# EV2760-VT-00A.net
KiCad netlist of a schematic drawn in Altium Designer
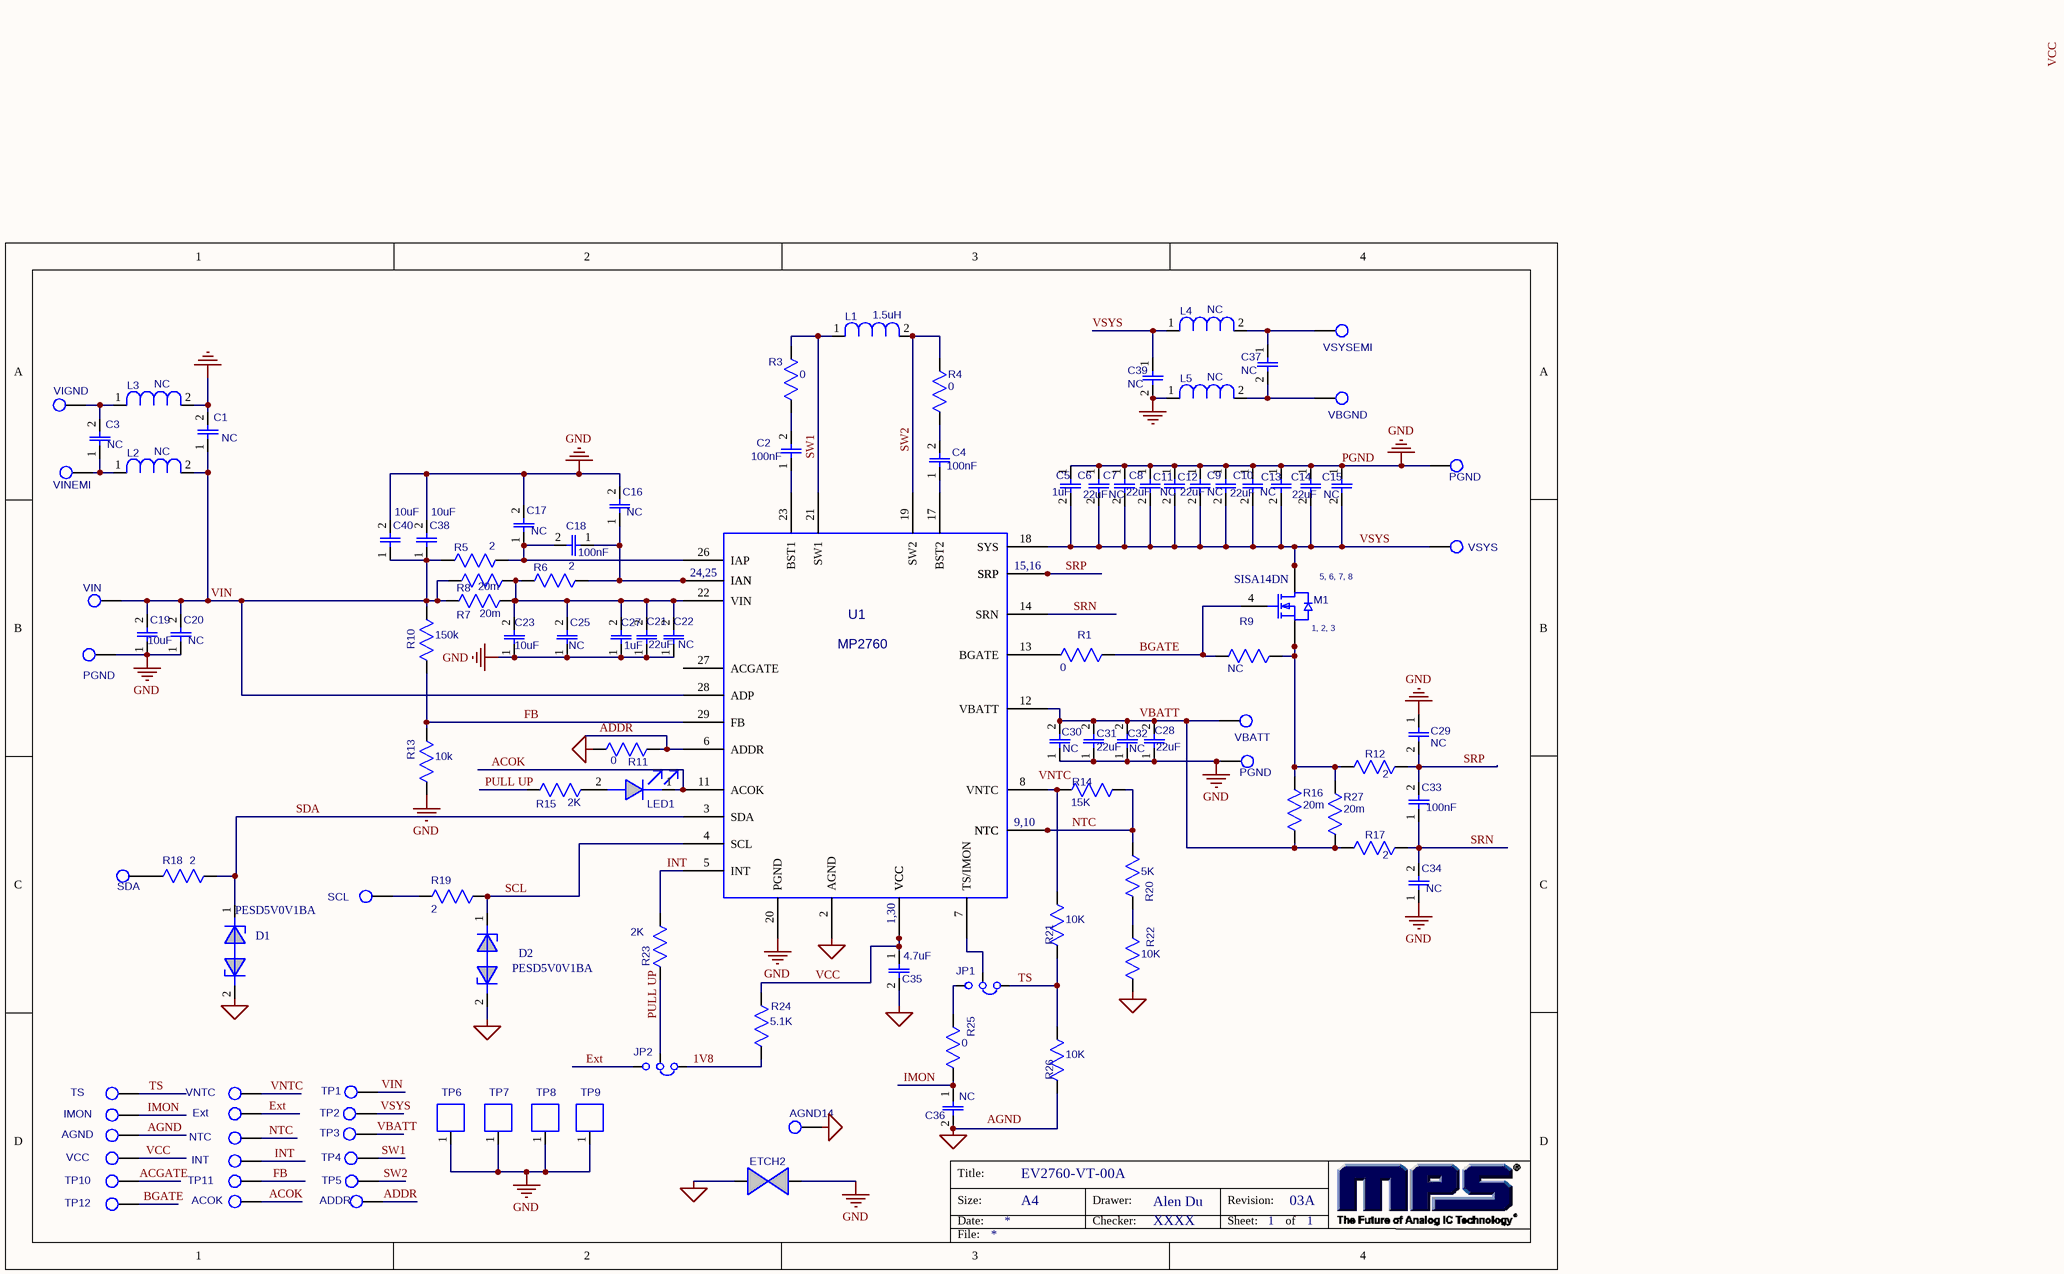
[diagram p0: EV2760-VT-00A.SchDoc]

(export (version "E")
  (design (tool "Eeschema 10.0.6"))
  (components
    (comp (ref "ACOK")
      (value "{Package}")
      (footprint "CONN/TP")
      (description "Connector;")
      (fields (field (name "MANUFACTURER") "{Manufacturer}") (field (name "PART NUMBER") "17.0017"))
      (libsource (lib "MPSLab") (part "CONN/TP"))
    )
    (comp (ref "ADDR")
      (value "{Package}")
      (footprint "CONN/TP")
      (description "Connector;")
      (fields (field (name "MANUFACTURER") "{Manufacturer}") (field (name "PART NUMBER") "17.0017"))
      (libsource (lib "MPSLab") (part "CONN/TP"))
    )
    (comp (ref "AGND")
      (value "{Package}")
      (footprint "CONN/TP")
      (description "Connector;")
      (fields (field (name "MANUFACTURER") "{Manufacturer}") (field (name "PART NUMBER") "17.0017"))
      (libsource (lib "MPSLab") (part "CONN/TP"))
    )
    (comp (ref "AGND14")
      (value "{Package}")
      (footprint "CONN/TP")
      (description "Connector;")
      (fields (field (name "MANUFACTURER") "{Manufacturer}") (field (name "PART NUMBER") "17.0017"))
      (libsource (lib "MPSLab") (part "CONN/TP"))
    )
    (comp (ref "C1")
      (value "NC")
      (footprint "CAP/0805")
      (description "Capacitor;25V;X5R")
      (fields (field (name "MANUFACTURER") "{Manufacturer}") (field (name "PART NUMBER") "07.0970"))
      (libsource (lib "MPSLab") (part "CAP/0805"))
    )
    (comp (ref "C2")
      (value "100nF")
      (footprint "CAP/0603")
      (description "Capacitor;25V;X5R")
      (fields (field (name "MANUFACTURER") "{Manufacturer}") (field (name "PART NUMBER") "07.0969"))
      (libsource (lib "MPSLab") (part "CAP/0603"))
    )
    (comp (ref "C3")
      (value "NC")
      (footprint "CAP/0805")
      (description "Capacitor;25V;X5R")
      (fields (field (name "MANUFACTURER") "{Manufacturer}") (field (name "PART NUMBER") "07.0970"))
      (libsource (lib "MPSLab") (part "CAP/0805"))
    )
    (comp (ref "C4")
      (value "100nF")
      (footprint "CAP/0603")
      (description "Capacitor;25V;X5R")
      (fields (field (name "MANUFACTURER") "{Manufacturer}") (field (name "PART NUMBER") "07.0969"))
      (libsource (lib "MPSLab") (part "CAP/0603"))
    )
    (comp (ref "C5")
      (value "1uF")
      (footprint "CAP/0603")
      (description "Ceramic Capacitor;25V;X7R;0603;")
      (fields (field (name "MANUFACTURER") "{Manufacturer}") (field (name "PART NUMBER") "07.0042"))
      (libsource (lib "MPSLab") (part "CAP/0603"))
    )
    (comp (ref "C6")
      (value "22uF")
      (footprint "CAP/0805")
      (description "Capacitor;25V;X5R")
      (fields (field (name "MANUFACTURER") "{Manufacturer}") (field (name "PART NUMBER") "07.1006"))
      (libsource (lib "MPSLab") (part "CAP/0805"))
    )
    (comp (ref "C7")
      (value "NC")
      (footprint "CAP/0805")
      (description "Capacitor;25V;X5R")
      (fields (field (name "MANUFACTURER") "{Manufacturer}") (field (name "PART NUMBER") "07.1006"))
      (libsource (lib "MPSLab") (part "CAP/0805"))
    )
    (comp (ref "C8")
      (value "22uF")
      (footprint "CAP/0805")
      (description "Capacitor;25V;X5R")
      (fields (field (name "MANUFACTURER") "{Manufacturer}") (field (name "PART NUMBER") "07.1006"))
      (libsource (lib "MPSLab") (part "CAP/0805"))
    )
    (comp (ref "C9")
      (value "NC")
      (footprint "CAP/0805")
      (description "Capacitor;25V;X5R")
      (fields (field (name "MANUFACTURER") "{Manufacturer}") (field (name "PART NUMBER") "07.1006"))
      (libsource (lib "MPSLab") (part "CAP/0805"))
    )
    (comp (ref "C10")
      (value "22uF")
      (footprint "CAP/0805")
      (description "Capacitor;25V;X5R")
      (fields (field (name "MANUFACTURER") "{Manufacturer}") (field (name "PART NUMBER") "07.1006"))
      (libsource (lib "MPSLab") (part "CAP/0805"))
    )
    (comp (ref "C11")
      (value "NC")
      (footprint "CAP/0805")
      (description "Capacitor;25V;X7R")
      (fields (field (name "MANUFACTURER") "{Manufacturer}") (field (name "PART NUMBER") "07.1121"))
      (libsource (lib "MPSLab") (part "CAP/0805"))
    )
    (comp (ref "C12")
      (value "22uF")
      (footprint "CAP/0805")
      (description "Capacitor;25V;X5R")
      (fields (field (name "MANUFACTURER") "{Manufacturer}") (field (name "PART NUMBER") "07.1006"))
      (libsource (lib "MPSLab") (part "CAP/0805"))
    )
    (comp (ref "C13")
      (value "NC")
      (footprint "CAP/0805")
      (description "Capacitor;25V;X5R")
      (fields (field (name "MANUFACTURER") "{Manufacturer}") (field (name "PART NUMBER") "07.1006"))
      (libsource (lib "MPSLab") (part "CAP/0805"))
    )
    (comp (ref "C14")
      (value "22uF")
      (footprint "CAP/0805")
      (description "Ceramic Capacitor;25V;X7R;0603;")
      (fields (field (name "MANUFACTURER") "{Manufacturer}") (field (name "PART NUMBER") "07.0042"))
      (libsource (lib "MPSLab") (part "CAP/0603"))
    )
    (comp (ref "C15")
      (value "NC")
      (footprint "CAP/0603")
      (description "Ceramic Capacitor;25V;X7R;0603;")
      (fields (field (name "MANUFACTURER") "{Manufacturer}") (field (name "PART NUMBER") "07.0042"))
      (libsource (lib "MPSLab") (part "CAP/0603"))
    )
    (comp (ref "C16")
      (value "NC")
      (footprint "CAP/0603")
      (description "Ceramic Capacitor;25V;X7R;0603;")
      (fields (field (name "MANUFACTURER") "{Manufacturer}") (field (name "PART NUMBER") "07.0042"))
      (libsource (lib "MPSLab") (part "CAP/0603"))
    )
    (comp (ref "C17")
      (value "NC")
      (footprint "CAP/0603")
      (description "Ceramic Capacitor;25V;X7R;0603;")
      (fields (field (name "MANUFACTURER") "{Manufacturer}") (field (name "PART NUMBER") "07.0042"))
      (libsource (lib "MPSLab") (part "CAP/0603"))
    )
    (comp (ref "C18")
      (value "100nF")
      (footprint "CAP/0603")
      (description "Ceramic Capacitor;50V;C0G;0603;")
      (fields (field (name "MANUFACTURER") "{Manufacturer}") (field (name "PART NUMBER") "07.0074"))
      (libsource (lib "MPSLab") (part "CAP/0603"))
    )
    (comp (ref "C19")
      (value "10uF")
      (footprint "CAP/0805")
      (description "Capacitor;25V;X5R")
      (fields (field (name "MANUFACTURER") "{Manufacturer}") (field (name "PART NUMBER") "07.0970"))
      (libsource (lib "MPSLab") (part "CAP/0805"))
    )
    (comp (ref "C20")
      (value "NC")
      (footprint "CAP/0805")
      (description "Capacitor;25V;X5R")
      (fields (field (name "MANUFACTURER") "{Manufacturer}") (field (name "PART NUMBER") "07.0970"))
      (libsource (lib "MPSLab") (part "CAP/0805"))
    )
    (comp (ref "C21")
      (value "22uF")
      (footprint "CAP/0603")
      (description "Ceramic Capacitor;25V;X7R;0603;")
      (fields (field (name "MANUFACTURER") "{Manufacturer}") (field (name "PART NUMBER") "07.0042"))
      (libsource (lib "MPSLab") (part "CAP/0603"))
    )
    (comp (ref "C22")
      (value "NC")
      (footprint "CAP/0603")
      (description "Ceramic Capacitor;25V;X7R;0603;")
      (fields (field (name "MANUFACTURER") "{Manufacturer}") (field (name "PART NUMBER") "07.0042"))
      (libsource (lib "MPSLab") (part "CAP/0603"))
    )
    (comp (ref "C23")
      (value "10uF")
      (footprint "CAP/0805")
      (description "Capacitor;25V;X5R")
      (fields (field (name "MANUFACTURER") "{Manufacturer}") (field (name "PART NUMBER") "07.0970"))
      (libsource (lib "MPSLab") (part "CAP/0805"))
    )
    (comp (ref "C25")
      (value "NC")
      (footprint "CAP/0805")
      (description "Capacitor;25V;X5R")
      (fields (field (name "MANUFACTURER") "{Manufacturer}") (field (name "PART NUMBER") "07.0970"))
      (libsource (lib "MPSLab") (part "CAP/0805"))
    )
    (comp (ref "C27")
      (value "1uF")
      (footprint "CAP/0603")
      (description "Ceramic Capacitor;25V;X7R;0603;")
      (fields (field (name "MANUFACTURER") "{Manufacturer}") (field (name "PART NUMBER") "07.0042"))
      (libsource (lib "MPSLab") (part "CAP/0603"))
    )
    (comp (ref "C28")
      (value "22uF")
      (footprint "CAP/0805")
      (description "Capacitor;25V;X5R")
      (fields (field (name "MANUFACTURER") "{Manufacturer}") (field (name "PART NUMBER") "07.1006"))
      (libsource (lib "MPSLab") (part "CAP/0805"))
    )
    (comp (ref "C29")
      (value "NC")
      (footprint "CAP/0603")
      (description "Ceramic Capacitor;25V;X7R;0603;")
      (fields (field (name "MANUFACTURER") "{Manufacturer}") (field (name "PART NUMBER") "07.0042"))
      (libsource (lib "MPSLab") (part "CAP/0603"))
    )
    (comp (ref "C30")
      (value "NC")
      (footprint "CAP/0805")
      (description "Capacitor;25V;X7R")
      (fields (field (name "MANUFACTURER") "{Manufacturer}") (field (name "PART NUMBER") "07.1121"))
      (libsource (lib "MPSLab") (part "CAP/0805"))
    )
    (comp (ref "C31")
      (value "22uF")
      (footprint "CAP/0805")
      (description "Capacitor;25V;X5R")
      (fields (field (name "MANUFACTURER") "{Manufacturer}") (field (name "PART NUMBER") "07.1006"))
      (libsource (lib "MPSLab") (part "CAP/0805"))
    )
    (comp (ref "C32")
      (value "NC")
      (footprint "CAP/0805")
      (description "Capacitor;25V;X5R")
      (fields (field (name "MANUFACTURER") "{Manufacturer}") (field (name "PART NUMBER") "07.1006"))
      (libsource (lib "MPSLab") (part "CAP/0805"))
    )
    (comp (ref "C33")
      (value "100nF")
      (footprint "CAP/0603")
      (description "Ceramic Capacitor;25V;X7R;0603;")
      (fields (field (name "MANUFACTURER") "{Manufacturer}") (field (name "PART NUMBER") "07.0042"))
      (libsource (lib "MPSLab") (part "CAP/0603"))
    )
    (comp (ref "C34")
      (value "NC")
      (footprint "CAP/0603")
      (description "Ceramic Capacitor;25V;X7R;0603;")
      (fields (field (name "MANUFACTURER") "{Manufacturer}") (field (name "PART NUMBER") "07.0042"))
      (libsource (lib "MPSLab") (part "CAP/0603"))
    )
    (comp (ref "C35")
      (value "4.7uF")
      (footprint "CAP/0603")
      (description "Ceramic Capacitor;50V;X7R;0603;")
      (fields (field (name "MANUFACTURER") "{Manufacturer}") (field (name "PART NUMBER") "07.0015"))
      (libsource (lib "MPSLab") (part "CAP/0603"))
    )
    (comp (ref "C36")
      (value "NC")
      (footprint "CAP/0603")
      (description "Ceramic Capacitor;50V;X7R;0603;")
      (fields (field (name "MANUFACTURER") "{Manufacturer}") (field (name "PART NUMBER") "07.0015"))
      (libsource (lib "MPSLab") (part "CAP/0603"))
    )
    (comp (ref "C37")
      (value "NC")
      (footprint "CAP/0603")
      (description "Ceramic Capacitor;25V;X7R;0603;")
      (fields (field (name "MANUFACTURER") "{Manufacturer}") (field (name "PART NUMBER") "07.0042"))
      (libsource (lib "MPSLab") (part "CAP/0603"))
    )
    (comp (ref "C38")
      (value "10uF")
      (footprint "CAP/0805")
      (description "Capacitor;25V;X5R")
      (fields (field (name "MANUFACTURER") "{Manufacturer}") (field (name "PART NUMBER") "07.0970"))
      (libsource (lib "MPSLab") (part "CAP/0805"))
    )
    (comp (ref "C39")
      (value "NC")
      (footprint "CAP/0603")
      (description "Ceramic Capacitor;25V;X7R;0603;")
      (fields (field (name "MANUFACTURER") "{Manufacturer}") (field (name "PART NUMBER") "07.0042"))
      (libsource (lib "MPSLab") (part "CAP/0603"))
    )
    (comp (ref "C40")
      (value "10uF")
      (footprint "CAP/0805")
      (description "Capacitor;25V;X5R")
      (fields (field (name "MANUFACTURER") "{Manufacturer}") (field (name "PART NUMBER") "07.0970"))
      (libsource (lib "MPSLab") (part "CAP/0805"))
    )
    (comp (ref "D1")
      (value "PESD5V0V1BA")
      (footprint "Diodes:SOD323/PESD5V0V1BA")
      (libsource (lib "Sheet1") (part "PESD5V0V1BA"))
    )
    (comp (ref "D2")
      (value "PESD5V0V1BA")
      (footprint "Diodes:SOD323/PESD5V0V1BA")
      (libsource (lib "Sheet1") (part "PESD5V0V1BA"))
    )
    (comp (ref "ETCH2")
      (value "ETCH0402")
      (footprint "ETCH0603")
      (description "{Description}")
      (fields (field (name "MANUFACTURER") "{Manufacturer}"))
      (libsource (lib "MPS_RESISTOR") (part "ETCH0402"))
    )
    (comp (ref "Ext")
      (value "{Package}")
      (footprint "CONN/TP")
      (description "Connector;")
      (fields (field (name "MANUFACTURER") "{Manufacturer}") (field (name "PART NUMBER") "17.0017"))
      (libsource (lib "MPSLab") (part "CONN/TP"))
    )
    (comp (ref "IMON")
      (value "{Package}")
      (footprint "CONN/TP")
      (description "Connector;")
      (fields (field (name "MANUFACTURER") "{Manufacturer}") (field (name "PART NUMBER") "17.0017"))
      (libsource (lib "MPSLab") (part "CONN/TP"))
    )
    (comp (ref "INT")
      (value "{Package}")
      (footprint "CONN/TP")
      (description "Connector;")
      (fields (field (name "MANUFACTURER") "{Manufacturer}") (field (name "PART NUMBER") "17.0017"))
      (libsource (lib "MPSLab") (part "CONN/TP"))
    )
    (comp (ref "JP1")
      (value "JUMPER/3PIN/DIP/2.54MM/B")
      (footprint "CONN/DIP/3PIN/2.54MM/A")
      (description "{Description}")
      (fields (field (name "MANUFACTURER") "{Manufacturer}"))
      (libsource (lib "Jumper") (part "JUMPER/3PIN/DIP/2.54MM/B"))
    )
    (comp (ref "JP2")
      (value "JUMPER/3PIN/DIP/2.54MM/B")
      (footprint "CONN/DIP/3PIN/2.54MM/A")
      (description "{Description}")
      (fields (field (name "MANUFACTURER") "{Manufacturer}"))
      (libsource (lib "Jumper") (part "JUMPER/3PIN/DIP/2.54MM/B"))
    )
    (comp (ref "L1")
      (value "1.5uH")
      (footprint "IND/Wurth/7447745022")
      (description "Inductor;2.2uH;0.0173ohms;8.2A")
      (fields (field (name "MANUFACTURER") "{Manufacturer}") (field (name "PART NUMBER") "03.0763"))
      (libsource (lib "MPSLab") (part "IND/TDK/SPM6530T-2R2M"))
    )
    (comp (ref "L2")
      (value "NC")
      (footprint "RES/0805")
      (description "Inductor;2.2uH;0.0173ohms;8.2A")
      (fields (field (name "MANUFACTURER") "{Manufacturer}") (field (name "PART NUMBER") "03.0616"))
      (libsource (lib "MPSLab") (part "IND/TDK/SPM6530T-2R2M"))
    )
    (comp (ref "L3")
      (value "NC")
      (footprint "RES/0805")
      (description "Inductor;2.2uH;0.0173ohms;8.2A")
      (fields (field (name "MANUFACTURER") "{Manufacturer}") (field (name "PART NUMBER") "03.0616"))
      (libsource (lib "MPSLab") (part "IND/TDK/SPM6530T-2R2M"))
    )
    (comp (ref "L4")
      (value "NC")
      (footprint "RES/0805")
      (description "Inductor;2.2uH;0.0173ohms;8.2A")
      (fields (field (name "MANUFACTURER") "{Manufacturer}") (field (name "PART NUMBER") "03.0616"))
      (libsource (lib "MPSLab") (part "IND/TDK/SPM6530T-2R2M"))
    )
    (comp (ref "L5")
      (value "NC")
      (footprint "RES/0805")
      (description "Inductor;2.2uH;0.0173ohms;8.2A")
      (fields (field (name "MANUFACTURER") "{Manufacturer}") (field (name "PART NUMBER") "03.0616"))
      (libsource (lib "MPSLab") (part "IND/TDK/SPM6530T-2R2M"))
    )
    (comp (ref "LED1")
      (value "LED/SMD/0805")
      (footprint "LED/SMD/0805")
      (description "LED;绿色;")
      (fields (field (name "MANUFACTURER") "{Manufacturer}") (field (name "PART NUMBER") "19.0009"))
      (libsource (lib "MPSLab") (part "LED/SMD/0805"))
    )
    (comp (ref "M1")
      (value "SISA14DN")
      (footprint "MOS/POWERPAK/1212-8")
      (description "N-Channel Mosfet;30V;6.2;27")
      (fields (field (name "PART NUMBER") "09.0001"))
      (libsource (lib "MPSLab") (part "SI7382DP"))
    )
    (comp (ref "NTC")
      (value "{Package}")
      (footprint "CONN/TP")
      (description "Connector;")
      (fields (field (name "MANUFACTURER") "{Manufacturer}") (field (name "PART NUMBER") "17.0017"))
      (libsource (lib "MPSLab") (part "CONN/TP"))
    )
    (comp (ref "PGND1")
      (value "PGND")
      (footprint "CONN/2MM")
      (description "Connector;")
      (fields (field (name "MANUFACTURER") "{Manufacturer}") (field (name "PART NUMBER") "17.0025"))
      (libsource (lib "MPSLab") (part "CONN/TP"))
    )
    (comp (ref "PGND2")
      (value "PGND")
      (footprint "CONN/2MM")
      (description "Connector;")
      (fields (field (name "MANUFACTURER") "{Manufacturer}") (field (name "PART NUMBER") "17.0025"))
      (libsource (lib "MPSLab") (part "CONN/TP"))
    )
    (comp (ref "PGND3")
      (value "PGND")
      (footprint "CONN/2MM")
      (description "Connector;")
      (fields (field (name "MANUFACTURER") "{Manufacturer}") (field (name "PART NUMBER") "17.0025"))
      (libsource (lib "MPSLab") (part "CONN/TP"))
    )
    (comp (ref "R1")
      (value "0")
      (footprint "RES/0603")
      (description "Film Resistor;5%;1/10W")
      (fields (field (name "MANUFACTURER") "Yageo") (field (name "PART NUMBER") "06.0007"))
      (libsource (lib "MPSLab") (part "RES/0603"))
    )
    (comp (ref "R3")
      (value "0")
      (footprint "RES/0603")
      (description "Resistor;1%")
      (fields (field (name "MANUFACTURER") "Yageo") (field (name "PART NUMBER") "06.1315"))
      (libsource (lib "MPSLab") (part "RES/0603"))
    )
    (comp (ref "R4")
      (value "0")
      (footprint "RES/0603")
      (description "Resistor;1%")
      (fields (field (name "MANUFACTURER") "Yageo") (field (name "PART NUMBER") "06.1315"))
      (libsource (lib "MPSLab") (part "RES/0603"))
    )
    (comp (ref "R5")
      (value "2")
      (footprint "RES/0603")
      (description "Resistor;1%")
      (fields (field (name "MANUFACTURER") "Yageo") (field (name "PART NUMBER") "06.1315"))
      (libsource (lib "MPSLab") (part "RES/0603"))
    )
    (comp (ref "R6")
      (value "2")
      (footprint "RES/0603")
      (description "Resistor;1%")
      (fields (field (name "MANUFACTURER") "Yageo") (field (name "PART NUMBER") "06.1315"))
      (libsource (lib "MPSLab") (part "RES/0603"))
    )
    (comp (ref "R7")
      (value "20m")
      (footprint "RES/2512")
      (description "Film Resistor;1%;1W;")
      (fields (field (name "MANUFACTURER") "Panasonic") (field (name "PART NUMBER") "06.0037"))
      (libsource (lib "MPSLab") (part "RES/2512"))
    )
    (comp (ref "R8")
      (value "20m")
      (footprint "RES/2512")
      (description "Film Resistor;1%;1W;")
      (fields (field (name "MANUFACTURER") "Panasonic") (field (name "PART NUMBER") "06.0037"))
      (libsource (lib "MPSLab") (part "RES/2512"))
    )
    (comp (ref "R9")
      (value "NC")
      (footprint "RES/0603")
      (description "Film Resistor;5%;1/10W")
      (fields (field (name "MANUFACTURER") "Yageo") (field (name "PART NUMBER") "06.0007"))
      (libsource (lib "MPSLab") (part "RES/0603"))
    )
    (comp (ref "R10")
      (value "150k")
      (footprint "RES/0603")
      (description "Film Resistor;5%;1/10W")
      (fields (field (name "MANUFACTURER") "Yageo") (field (name "PART NUMBER") "06.0007"))
      (libsource (lib "MPSLab") (part "RES/0603"))
    )
    (comp (ref "R11")
      (value "0")
      (footprint "RES/0603")
      (description "Film Resistor;5%;1/10W")
      (fields (field (name "MANUFACTURER") "Yageo") (field (name "PART NUMBER") "06.0007"))
      (libsource (lib "MPSLab") (part "RES/0603"))
    )
    (comp (ref "R12")
      (value "2")
      (footprint "RES/0603")
      (description "Film Resistor;5%;1/10W")
      (fields (field (name "MANUFACTURER") "Yageo") (field (name "PART NUMBER") "06.0007"))
      (libsource (lib "MPSLab") (part "RES/0603"))
    )
    (comp (ref "R13")
      (value "10k")
      (footprint "RES/0603")
      (description "Film Resistor;5%;1/10W")
      (fields (field (name "MANUFACTURER") "Yageo") (field (name "PART NUMBER") "06.0007"))
      (libsource (lib "MPSLab") (part "RES/0603"))
    )
    (comp (ref "R14")
      (value "15K")
      (footprint "RES/0603")
      (description "Film Resistor;5%;1/10W")
      (fields (field (name "MANUFACTURER") "Yageo") (field (name "PART NUMBER") "06.0007"))
      (libsource (lib "MPSLab") (part "RES/0603"))
    )
    (comp (ref "R15")
      (value "2K")
      (footprint "RES/0603")
      (description "Film Resistor;1%;")
      (fields (field (name "MANUFACTURER") "Yageo") (field (name "PART NUMBER") "06.0092"))
      (libsource (lib "MPSLab") (part "RES/0603"))
    )
    (comp (ref "R16")
      (value "20m")
      (footprint "RES/1206")
      (description "Film Resistor;1%;1W;")
      (fields (field (name "MANUFACTURER") "Panasonic") (field (name "PART NUMBER") "06.0037"))
      (libsource (lib "MPSLab") (part "RES/2512"))
    )
    (comp (ref "R17")
      (value "2")
      (footprint "RES/0603")
      (description "Film Resistor;5%;1/10W")
      (fields (field (name "MANUFACTURER") "Yageo") (field (name "PART NUMBER") "06.0007"))
      (libsource (lib "MPSLab") (part "RES/0603"))
    )
    (comp (ref "R18")
      (value "2")
      (footprint "RES/0603")
      (description "Film Resistor;1%")
      (fields (field (name "MANUFACTURER") "Yageo") (field (name "PART NUMBER") "06.0966"))
      (libsource (lib "MPSLab") (part "RES/0603"))
    )
    (comp (ref "R19")
      (value "2")
      (footprint "RES/0603")
      (description "Film Resistor;1%")
      (fields (field (name "MANUFACTURER") "Yageo") (field (name "PART NUMBER") "06.0966"))
      (libsource (lib "MPSLab") (part "RES/0603"))
    )
    (comp (ref "R20")
      (value "5K")
      (footprint "RES/0603")
      (description "Film Resistor;5%;1/10W")
      (fields (field (name "MANUFACTURER") "Yageo") (field (name "PART NUMBER") "06.0007"))
      (libsource (lib "MPSLab") (part "RES/0603"))
    )
    (comp (ref "R21")
      (value "10K")
      (footprint "RES/0603")
      (description "Film Resistor;5%;1/10W")
      (fields (field (name "MANUFACTURER") "Yageo") (field (name "PART NUMBER") "06.0007"))
      (libsource (lib "MPSLab") (part "RES/0603"))
    )
    (comp (ref "R22")
      (value "10K")
      (footprint "RES/0603")
      (description "Film Resistor;5%;1/10W")
      (fields (field (name "MANUFACTURER") "Yageo") (field (name "PART NUMBER") "06.0007"))
      (libsource (lib "MPSLab") (part "RES/0603"))
    )
    (comp (ref "R23")
      (value "2K")
      (footprint "RES/0603")
      (description "Film Resistor;5%;1/10W")
      (fields (field (name "MANUFACTURER") "Yageo") (field (name "PART NUMBER") "06.0007"))
      (libsource (lib "MPSLab") (part "RES/0603"))
    )
    (comp (ref "R24")
      (value "5.1K")
      (footprint "RES/0603")
      (description "Film Resistor;1%;")
      (fields (field (name "MANUFACTURER") "Yageo") (field (name "PART NUMBER") "06.0691"))
      (libsource (lib "MPSLab") (part "RES/0603"))
    )
    (comp (ref "R25")
      (value "0")
      (footprint "RES/0603")
      (description "Film Resistor;5%;1/10W")
      (fields (field (name "MANUFACTURER") "Yageo") (field (name "PART NUMBER") "06.0007"))
      (libsource (lib "MPSLab") (part "RES/0603"))
    )
    (comp (ref "R26")
      (value "10K")
      (footprint "RES/0603")
      (description "Film Resistor;5%;1/10W")
      (fields (field (name "MANUFACTURER") "Yageo") (field (name "PART NUMBER") "06.0007"))
      (libsource (lib "MPSLab") (part "RES/0603"))
    )
    (comp (ref "R27")
      (value "20m")
      (footprint "RES/1206")
      (description "Film Resistor;1%;1W;")
      (fields (field (name "MANUFACTURER") "Panasonic") (field (name "PART NUMBER") "06.0037"))
      (libsource (lib "MPSLab") (part "RES/2512"))
    )
    (comp (ref "SCL")
      (value "SCL")
      (footprint "CONN/TP")
      (description "Connector;")
      (fields (field (name "MANUFACTURER") "{Manufacturer}") (field (name "PART NUMBER") "17.0017"))
      (libsource (lib "MPSLab") (part "CONN/TP"))
    )
    (comp (ref "SDA")
      (value "SDA")
      (footprint "CONN/TP")
      (description "Connector;")
      (fields (field (name "MANUFACTURER") "{Manufacturer}") (field (name "PART NUMBER") "17.0017"))
      (libsource (lib "MPSLab") (part "CONN/TP"))
    )
    (comp (ref "TP1")
      (value "{Package}")
      (footprint "CONN/TP")
      (description "Connector;")
      (fields (field (name "MANUFACTURER") "{Manufacturer}") (field (name "PART NUMBER") "17.0266"))
      (libsource (lib "MPSLab") (part "CONN/TP"))
    )
    (comp (ref "TP2")
      (value "{Package}")
      (footprint "CONN/TP")
      (description "Connector;")
      (fields (field (name "MANUFACTURER") "{Manufacturer}") (field (name "PART NUMBER") "17.0266"))
      (libsource (lib "MPSLab") (part "CONN/TP"))
    )
    (comp (ref "TP3")
      (value "{Package}")
      (footprint "CONN/TP")
      (description "Connector;")
      (fields (field (name "MANUFACTURER") "{Manufacturer}") (field (name "PART NUMBER") "17.0266"))
      (libsource (lib "MPSLab") (part "CONN/TP"))
    )
    (comp (ref "TP4")
      (value "{Package}")
      (footprint "CONN/TP")
      (description "Connector;")
      (fields (field (name "MANUFACTURER") "{Manufacturer}") (field (name "PART NUMBER") "17.0266"))
      (libsource (lib "MPSLab") (part "CONN/TP"))
    )
    (comp (ref "TP5")
      (value "{Package}")
      (footprint "CONN/TP")
      (description "Connector;")
      (fields (field (name "MANUFACTURER") "{Manufacturer}") (field (name "PART NUMBER") "17.0266"))
      (libsource (lib "MPSLab") (part "CONN/TP"))
    )
    (comp (ref "TP6")
      (value "接地测试点")
      (footprint "TP - GND")
      (description "Connector")
      (fields (field (name "MANUFACTURER") "{Manufacturer}") (field (name "PART NUMBER") "17.0265"))
      (libsource (lib "MPSLab") (part "CONN/白色铜柱"))
    )
    (comp (ref "TP7")
      (value "接地测试点")
      (footprint "TP - GND")
      (description "Connector")
      (fields (field (name "MANUFACTURER") "{Manufacturer}") (field (name "PART NUMBER") "17.0265"))
      (libsource (lib "MPSLab") (part "CONN/白色铜柱"))
    )
    (comp (ref "TP8")
      (value "接地测试点")
      (footprint "TP - GND")
      (description "Connector")
      (fields (field (name "MANUFACTURER") "{Manufacturer}") (field (name "PART NUMBER") "17.0265"))
      (libsource (lib "MPSLab") (part "CONN/白色铜柱"))
    )
    (comp (ref "TP9")
      (value "接地测试点")
      (footprint "TP - GND")
      (description "Connector")
      (fields (field (name "MANUFACTURER") "{Manufacturer}") (field (name "PART NUMBER") "17.0265"))
      (libsource (lib "MPSLab") (part "CONN/白色铜柱"))
    )
    (comp (ref "TP10")
      (value "{Package}")
      (footprint "CONN/TP")
      (description "Connector;")
      (fields (field (name "MANUFACTURER") "{Manufacturer}") (field (name "PART NUMBER") "17.0017"))
      (libsource (lib "MPSLab") (part "CONN/TP"))
    )
    (comp (ref "TP11")
      (value "{Package}")
      (footprint "CONN/TP")
      (description "Connector;")
      (fields (field (name "MANUFACTURER") "{Manufacturer}") (field (name "PART NUMBER") "17.0017"))
      (libsource (lib "MPSLab") (part "CONN/TP"))
    )
    (comp (ref "TP12")
      (value "{Package}")
      (footprint "CONN/TP")
      (description "Connector;")
      (fields (field (name "MANUFACTURER") "{Manufacturer}") (field (name "PART NUMBER") "17.0017"))
      (libsource (lib "MPSLab") (part "CONN/TP"))
    )
    (comp (ref "TS")
      (value "{Package}")
      (footprint "CONN/TP")
      (description "Connector;")
      (fields (field (name "MANUFACTURER") "{Manufacturer}") (field (name "PART NUMBER") "17.0017"))
      (libsource (lib "MPSLab") (part "CONN/TP"))
    )
    (comp (ref "U1")
      (value "MP2760")
      (footprint "FCQFN30L/4*5MM")
      (description "{Description}")
      (fields (field (name "MANUFACTURER") "{Manufacturer}"))
      (libsource (lib "T-EV2651-V-00A - Copy") (part "MP2651GV"))
    )
    (comp (ref "VBATT")
      (value "VBATT")
      (footprint "CONN/2MM")
      (description "Connector;")
      (fields (field (name "MANUFACTURER") "{Manufacturer}") (field (name "PART NUMBER") "17.0025"))
      (libsource (lib "MPSLab") (part "CONN/TP"))
    )
    (comp (ref "VBEMI")
      (value "VSYSEMI")
      (footprint "CONN/2MM")
      (description "Connector;")
      (fields (field (name "MANUFACTURER") "{Manufacturer}") (field (name "PART NUMBER") "17.0025"))
      (libsource (lib "MPSLab") (part "CONN/TP"))
    )
    (comp (ref "VBGND")
      (value "VBGND")
      (footprint "CONN/2MM")
      (description "Connector;")
      (fields (field (name "MANUFACTURER") "{Manufacturer}") (field (name "PART NUMBER") "17.0025"))
      (libsource (lib "MPSLab") (part "CONN/TP"))
    )
    (comp (ref "VCC")
      (value "{Package}")
      (footprint "CONN/TP")
      (description "Connector;")
      (fields (field (name "MANUFACTURER") "{Manufacturer}") (field (name "PART NUMBER") "17.0017"))
      (libsource (lib "MPSLab") (part "CONN/TP"))
    )
    (comp (ref "VIEMI")
      (value "VINEMI")
      (footprint "CONN/2MM")
      (description "Connector;")
      (fields (field (name "MANUFACTURER") "{Manufacturer}") (field (name "PART NUMBER") "17.0025"))
      (libsource (lib "MPSLab") (part "CONN/TP"))
    )
    (comp (ref "VIGND")
      (value "VINGND")
      (footprint "CONN/2MM")
      (description "Connector;")
      (fields (field (name "MANUFACTURER") "{Manufacturer}") (field (name "PART NUMBER") "17.0025"))
      (libsource (lib "MPSLab") (part "CONN/TP"))
    )
    (comp (ref "VIN2")
      (value "VIN")
      (footprint "CONN/2MM")
      (description "Connector;")
      (fields (field (name "MANUFACTURER") "{Manufacturer}") (field (name "PART NUMBER") "17.0025"))
      (libsource (lib "MPSLab") (part "CONN/TP"))
    )
    (comp (ref "VNTC")
      (value "{Package}")
      (footprint "CONN/TP")
      (description "Connector;")
      (fields (field (name "MANUFACTURER") "{Manufacturer}") (field (name "PART NUMBER") "17.0017"))
      (libsource (lib "MPSLab") (part "CONN/TP"))
    )
    (comp (ref "VSYS1")
      (value "VSYS")
      (footprint "CONN/2MM")
      (description "Connector;")
      (fields (field (name "MANUFACTURER") "{Manufacturer}") (field (name "PART NUMBER") "17.0025"))
      (libsource (lib "MPSLab") (part "CONN/TP"))
    )
  )
  (nets
    (net (code "1") (name "/1V8") (class "Default")
      (node (ref "JP2") (pin "1") (pinfunction "1_1") (pintype "passive"))
      (node (ref "R24") (pin "1") (pintype "passive"))
    )
    (net (code "2") (name "/ACGATE") (class "Default") (node (ref "TP10") (pin "1") (pintype "passive")))
    (net (code "3") (name "/ACOK") (class "Default")
      (node (ref "ACOK") (pin "1") (pintype "passive"))
      (node (ref "LED1") (pin "1") (pintype "passive"))
      (node (ref "U1") (pin "11") (pinfunction "ACOK_11") (pintype "passive"))
    )
    (net (code "4") (name "/ADDR") (class "Default")
      (node (ref "ADDR") (pin "1") (pintype "passive"))
      (node (ref "R11") (pin "2") (pintype "passive"))
      (node (ref "U1") (pin "6") (pinfunction "ADDR_6") (pintype "passive"))
    )
    (net (code "5") (name "/BGATE") (class "Default")
      (node (ref "M1") (pin "4") (pinfunction "G_4") (pintype "passive"))
      (node (ref "R1") (pin "2") (pintype "passive"))
      (node (ref "R9") (pin "1") (pintype "passive"))
      (node (ref "TP12") (pin "1") (pintype "passive"))
    )
    (net (code "6") (name "/Ext") (class "Default")
      (node (ref "Ext") (pin "1") (pintype "passive"))
      (node (ref "JP2") (pin "3") (pinfunction "3_3") (pintype "passive"))
    )
    (net (code "7") (name "/FB") (class "Default")
      (node (ref "R10") (pin "1") (pintype "passive"))
      (node (ref "R13") (pin "2") (pintype "passive"))
      (node (ref "TP11") (pin "1") (pintype "passive"))
      (node (ref "U1") (pin "29") (pinfunction "FB_29") (pintype "passive"))
    )
    (net (code "8") (name "/IMON") (class "Default")
      (node (ref "C36") (pin "1") (pintype "passive"))
      (node (ref "IMON") (pin "1") (pintype "passive"))
      (node (ref "R25") (pin "1") (pintype "passive"))
    )
    (net (code "9") (name "/INT") (class "Default")
      (node (ref "INT") (pin "1") (pintype "passive"))
      (node (ref "R23") (pin "1") (pintype "passive"))
      (node (ref "U1") (pin "5") (pinfunction "INT_5") (pintype "passive"))
    )
    (net (code "10") (name "/NTC") (class "Default")
      (node (ref "NTC") (pin "1") (pintype "passive"))
      (node (ref "R14") (pin "1") (pintype "passive"))
      (node (ref "R20") (pin "2") (pintype "passive"))
      (node (ref "U1") (pin "10") (pinfunction "NTC_10") (pintype "passive"))
      (node (ref "U1") (pin "9") (pinfunction "NTC_9") (pintype "passive"))
    )
    (net (code "11") (name "/PULL UP") (class "Default")
      (node (ref "JP2") (pin "2") (pinfunction "2_2") (pintype "passive"))
      (node (ref "R15") (pin "1") (pintype "passive"))
      (node (ref "R23") (pin "2") (pintype "passive"))
    )
    (net (code "12") (name "/SCL") (class "Default")
      (node (ref "D2") (pin "1") (pinfunction "1_1") (pintype "passive"))
      (node (ref "R19") (pin "2") (pintype "passive"))
      (node (ref "U1") (pin "4") (pinfunction "SCL_4") (pintype "passive"))
    )
    (net (code "13") (name "/SDA") (class "Default")
      (node (ref "D1") (pin "1") (pinfunction "1_1") (pintype "passive"))
      (node (ref "R18") (pin "1") (pintype "passive"))
      (node (ref "U1") (pin "3") (pinfunction "SDA_3") (pintype "passive"))
    )
    (net (code "14") (name "/SRN") (class "Default")
      (node (ref "C33") (pin "1") (pintype "passive"))
      (node (ref "C34") (pin "2") (pintype "passive"))
      (node (ref "R17") (pin "2") (pintype "passive"))
      (node (ref "U1") (pin "14") (pinfunction "SRN_14") (pintype "passive"))
    )
    (net (code "15") (name "/SRP") (class "Default")
      (node (ref "C29") (pin "2") (pintype "passive"))
      (node (ref "C33") (pin "2") (pintype "passive"))
      (node (ref "R12") (pin "2") (pintype "passive"))
      (node (ref "U1") (pin "15") (pinfunction "SRP_15") (pintype "passive"))
      (node (ref "U1") (pin "16") (pinfunction "SRP_16") (pintype "passive"))
    )
    (net (code "16") (name "/SW1") (class "Default")
      (node (ref "L1") (pin "1") (pintype "passive"))
      (node (ref "R3") (pin "2") (pintype "passive"))
      (node (ref "TP4") (pin "1") (pintype "passive"))
      (node (ref "U1") (pin "21") (pinfunction "SW1_21") (pintype "passive"))
    )
    (net (code "17") (name "/SW2") (class "Default")
      (node (ref "L1") (pin "2") (pintype "passive"))
      (node (ref "R4") (pin "1") (pintype "passive"))
      (node (ref "TP5") (pin "1") (pintype "passive"))
      (node (ref "U1") (pin "19") (pinfunction "SW2_19") (pintype "passive"))
    )
    (net (code "18") (name "/TS") (class "Default")
      (node (ref "JP1") (pin "1") (pinfunction "1_1") (pintype "passive"))
      (node (ref "R21") (pin "2") (pintype "passive"))
      (node (ref "R26") (pin "1") (pintype "passive"))
      (node (ref "TS") (pin "1") (pintype "passive"))
    )
    (net (code "19") (name "/VBATT") (class "Default")
      (node (ref "C28") (pin "2") (pintype "passive"))
      (node (ref "C30") (pin "2") (pintype "passive"))
      (node (ref "C31") (pin "2") (pintype "passive"))
      (node (ref "C32") (pin "2") (pintype "passive"))
      (node (ref "R16") (pin "1") (pintype "passive"))
      (node (ref "R17") (pin "1") (pintype "passive"))
      (node (ref "R27") (pin "1") (pintype "passive"))
      (node (ref "TP3") (pin "1") (pintype "passive"))
      (node (ref "U1") (pin "12") (pinfunction "VBATT_12") (pintype "passive"))
      (node (ref "VBATT") (pin "1") (pintype "passive"))
    )
    (net (code "20") (name "/VCC") (class "Default")
      (node (ref "C35") (pin "1") (pintype "passive"))
      (node (ref "R24") (pin "2") (pintype "passive"))
      (node (ref "U1") (pin "1") (pinfunction "VCC_1") (pintype "passive"))
      (node (ref "U1") (pin "30") (pinfunction "VCC_30") (pintype "passive"))
      (node (ref "VCC") (pin "1") (pintype "passive"))
    )
    (net (code "21") (name "/VIN") (class "Default")
      (node (ref "C1") (pin "1") (pintype "passive"))
      (node (ref "C19") (pin "2") (pintype "passive"))
      (node (ref "C20") (pin "2") (pintype "passive"))
      (node (ref "C38") (pin "1") (pintype "passive"))
      (node (ref "C40") (pin "1") (pintype "passive"))
      (node (ref "L2") (pin "2") (pintype "passive"))
      (node (ref "R10") (pin "2") (pintype "passive"))
      (node (ref "R5") (pin "1") (pintype "passive"))
      (node (ref "R7") (pin "1") (pintype "passive"))
      (node (ref "R8") (pin "1") (pintype "passive"))
      (node (ref "TP1") (pin "1") (pintype "passive"))
      (node (ref "U1") (pin "28") (pinfunction "ADP_28") (pintype "passive"))
      (node (ref "VIN2") (pin "1") (pintype "passive"))
    )
    (net (code "22") (name "/VNTC") (class "Default") (node (ref "VNTC") (pin "1") (pintype "passive")))
    (net (code "23") (name "/VSYS") (class "Default")
      (node (ref "C10") (pin "2") (pintype "passive"))
      (node (ref "C11") (pin "2") (pintype "passive"))
      (node (ref "C12") (pin "2") (pintype "passive"))
      (node (ref "C13") (pin "2") (pintype "passive"))
      (node (ref "C14") (pin "2") (pintype "passive"))
      (node (ref "C15") (pin "2") (pintype "passive"))
      (node (ref "C39") (pin "1") (pintype "passive"))
      (node (ref "C5") (pin "2") (pintype "passive"))
      (node (ref "C6") (pin "2") (pintype "passive"))
      (node (ref "C7") (pin "2") (pintype "passive"))
      (node (ref "C8") (pin "2") (pintype "passive"))
      (node (ref "C9") (pin "2") (pintype "passive"))
      (node (ref "L4") (pin "1") (pintype "passive"))
      (node (ref "M1") (pin "5") (pinfunction "D_5") (pintype "passive"))
      (node (ref "M1") (pin "6") (pinfunction "D_6") (pintype "passive"))
      (node (ref "M1") (pin "7") (pinfunction "D_7") (pintype "passive"))
      (node (ref "M1") (pin "8") (pinfunction "D_8") (pintype "passive"))
      (node (ref "TP2") (pin "1") (pintype "passive"))
      (node (ref "U1") (pin "18") (pinfunction "SYS_18") (pintype "passive"))
      (node (ref "VSYS1") (pin "1") (pintype "passive"))
    )
    (net (code "24") (name "AGND") (class "Default")
      (node (ref "AGND") (pin "1") (pintype "passive"))
      (node (ref "AGND14") (pin "1") (pintype "passive"))
      (node (ref "C35") (pin "2") (pintype "passive"))
      (node (ref "C36") (pin "2") (pintype "passive"))
      (node (ref "D1") (pin "2") (pinfunction "2_2") (pintype "passive"))
      (node (ref "D2") (pin "2") (pinfunction "2_2") (pintype "passive"))
      (node (ref "ETCH2") (pin "1") (pinfunction "1_1") (pintype "passive"))
      (node (ref "R11") (pin "1") (pintype "passive"))
      (node (ref "R22") (pin "1") (pintype "passive"))
      (node (ref "R26") (pin "2") (pintype "passive"))
      (node (ref "U1") (pin "2") (pinfunction "AGND_2") (pintype "passive"))
    )
    (net (code "25") (name "GND") (class "Default")
      (node (ref "C1") (pin "2") (pintype "passive"))
      (node (ref "C10") (pin "1") (pintype "passive"))
      (node (ref "C11") (pin "1") (pintype "passive"))
      (node (ref "C12") (pin "1") (pintype "passive"))
      (node (ref "C13") (pin "1") (pintype "passive"))
      (node (ref "C14") (pin "1") (pintype "passive"))
      (node (ref "C15") (pin "1") (pintype "passive"))
      (node (ref "C16") (pin "2") (pintype "passive"))
      (node (ref "C17") (pin "2") (pintype "passive"))
      (node (ref "C19") (pin "1") (pintype "passive"))
      (node (ref "C20") (pin "1") (pintype "passive"))
      (node (ref "C21") (pin "1") (pintype "passive"))
      (node (ref "C22") (pin "1") (pintype "passive"))
      (node (ref "C23") (pin "1") (pintype "passive"))
      (node (ref "C25") (pin "1") (pintype "passive"))
      (node (ref "C27") (pin "1") (pintype "passive"))
      (node (ref "C28") (pin "1") (pintype "passive"))
      (node (ref "C29") (pin "1") (pintype "passive"))
      (node (ref "C30") (pin "1") (pintype "passive"))
      (node (ref "C31") (pin "1") (pintype "passive"))
      (node (ref "C32") (pin "1") (pintype "passive"))
      (node (ref "C34") (pin "1") (pintype "passive"))
      (node (ref "C38") (pin "2") (pintype "passive"))
      (node (ref "C39") (pin "2") (pintype "passive"))
      (node (ref "C40") (pin "2") (pintype "passive"))
      (node (ref "C5") (pin "1") (pintype "passive"))
      (node (ref "C6") (pin "1") (pintype "passive"))
      (node (ref "C7") (pin "1") (pintype "passive"))
      (node (ref "C8") (pin "1") (pintype "passive"))
      (node (ref "C9") (pin "1") (pintype "passive"))
      (node (ref "ETCH2") (pin "2") (pinfunction "2_2") (pintype "passive"))
      (node (ref "L3") (pin "2") (pintype "passive"))
      (node (ref "L5") (pin "1") (pintype "passive"))
      (node (ref "PGND1") (pin "1") (pintype "passive"))
      (node (ref "PGND2") (pin "1") (pintype "passive"))
      (node (ref "PGND3") (pin "1") (pintype "passive"))
      (node (ref "R13") (pin "1") (pintype "passive"))
      (node (ref "TP6") (pin "1") (pintype "passive"))
      (node (ref "TP7") (pin "1") (pintype "passive"))
      (node (ref "TP8") (pin "1") (pintype "passive"))
      (node (ref "TP9") (pin "1") (pintype "passive"))
      (node (ref "U1") (pin "20") (pinfunction "PGND_20") (pintype "passive"))
    )
    (net (code "26") (name "Net-(C2-Pad2)") (class "Default")
      (node (ref "C2") (pin "2") (pintype "passive"))
      (node (ref "R3") (pin "1") (pintype "passive"))
    )
    (net (code "27") (name "Net-(C3-Pad1)") (class "Default")
      (node (ref "C3") (pin "1") (pintype "passive"))
      (node (ref "L2") (pin "1") (pintype "passive"))
      (node (ref "VIEMI") (pin "1") (pintype "passive"))
    )
    (net (code "28") (name "Net-(C3-Pad2)") (class "Default")
      (node (ref "C3") (pin "2") (pintype "passive"))
      (node (ref "L3") (pin "1") (pintype "passive"))
      (node (ref "VIGND") (pin "1") (pintype "passive"))
    )
    (net (code "29") (name "Net-(C4-Pad2)") (class "Default")
      (node (ref "C4") (pin "2") (pintype "passive"))
      (node (ref "R4") (pin "2") (pintype "passive"))
    )
    (net (code "30") (name "Net-(C16-Pad1)") (class "Default")
      (node (ref "C16") (pin "1") (pintype "passive"))
      (node (ref "C18") (pin "1") (pintype "passive"))
      (node (ref "R6") (pin "2") (pintype "passive"))
      (node (ref "U1") (pin "24") (pinfunction "IAN_24") (pintype "passive"))
      (node (ref "U1") (pin "25") (pinfunction "IAN_25") (pintype "passive"))
    )
    (net (code "31") (name "Net-(C37-Pad1)") (class "Default")
      (node (ref "C37") (pin "1") (pintype "passive"))
      (node (ref "L4") (pin "2") (pintype "passive"))
      (node (ref "VBEMI") (pin "1") (pintype "passive"))
    )
    (net (code "32") (name "Net-(C37-Pad2)") (class "Default")
      (node (ref "C37") (pin "2") (pintype "passive"))
      (node (ref "L5") (pin "2") (pintype "passive"))
      (node (ref "VBGND") (pin "1") (pintype "passive"))
    )
    (net (code "33") (name "Net-(JP1-Pad3)") (class "Default")
      (node (ref "JP1") (pin "3") (pinfunction "3_3") (pintype "passive"))
      (node (ref "R25") (pin "2") (pintype "passive"))
    )
    (net (code "34") (name "Net-(LED1-Pad2)") (class "Default")
      (node (ref "LED1") (pin "2") (pintype "passive"))
      (node (ref "R15") (pin "2") (pintype "passive"))
    )
    (net (code "35") (name "Net-(M1-S-Pad1)") (class "Default")
      (node (ref "M1") (pin "1") (pinfunction "S_1") (pintype "passive"))
      (node (ref "M1") (pin "2") (pinfunction "S_2") (pintype "passive"))
      (node (ref "M1") (pin "3") (pinfunction "S_3") (pintype "passive"))
      (node (ref "R12") (pin "1") (pintype "passive"))
      (node (ref "R16") (pin "2") (pintype "passive"))
      (node (ref "R27") (pin "2") (pintype "passive"))
      (node (ref "R9") (pin "2") (pintype "passive"))
    )
    (net (code "36") (name "Net-(R18-Pad2)") (class "Default")
      (node (ref "R18") (pin "2") (pintype "passive"))
      (node (ref "SDA") (pin "1") (pintype "passive"))
    )
    (net (code "37") (name "Net-(R19-Pad1)") (class "Default")
      (node (ref "R19") (pin "1") (pintype "passive"))
      (node (ref "SCL") (pin "1") (pintype "passive"))
    )
    (net (code "38") (name "Net-(R20-Pad1)") (class "Default")
      (node (ref "R20") (pin "1") (pintype "passive"))
      (node (ref "R22") (pin "2") (pintype "passive"))
    )
    (net (code "39") (name "Net-(U1-BGATE)") (class "Default")
      (node (ref "R1") (pin "1") (pintype "passive"))
      (node (ref "U1") (pin "13") (pinfunction "BGATE_13") (pintype "passive"))
    )
    (net (code "40") (name "Net-(U1-BST1)") (class "Default")
      (node (ref "C2") (pin "1") (pintype "passive"))
      (node (ref "U1") (pin "23") (pinfunction "BST1_23") (pintype "passive"))
    )
    (net (code "41") (name "Net-(U1-BST2)") (class "Default")
      (node (ref "C4") (pin "1") (pintype "passive"))
      (node (ref "U1") (pin "17") (pinfunction "BST2_17") (pintype "passive"))
    )
    (net (code "42") (name "Net-(U1-IAP)") (class "Default")
      (node (ref "C17") (pin "1") (pintype "passive"))
      (node (ref "C18") (pin "2") (pintype "passive"))
      (node (ref "R5") (pin "2") (pintype "passive"))
      (node (ref "U1") (pin "26") (pinfunction "IAP_26") (pintype "passive"))
    )
    (net (code "43") (name "Net-(U1-TS{slash}IMON)") (class "Default")
      (node (ref "JP1") (pin "2") (pinfunction "2_2") (pintype "passive"))
      (node (ref "U1") (pin "7") (pinfunction "TS/IMON_7") (pintype "passive"))
    )
    (net (code "44") (name "Net-(U1-VIN)") (class "Default")
      (node (ref "C21") (pin "2") (pintype "passive"))
      (node (ref "C22") (pin "2") (pintype "passive"))
      (node (ref "C23") (pin "2") (pintype "passive"))
      (node (ref "C25") (pin "2") (pintype "passive"))
      (node (ref "C27") (pin "2") (pintype "passive"))
      (node (ref "R6") (pin "1") (pintype "passive"))
      (node (ref "R7") (pin "2") (pintype "passive"))
      (node (ref "R8") (pin "2") (pintype "passive"))
      (node (ref "U1") (pin "22") (pinfunction "VIN_22") (pintype "passive"))
    )
    (net (code "45") (name "Net-(U1-VNTC)") (class "Default")
      (node (ref "R14") (pin "2") (pintype "passive"))
      (node (ref "R21") (pin "1") (pintype "passive"))
      (node (ref "U1") (pin "8") (pinfunction "VNTC_8") (pintype "passive"))
    )
    (net (code "46") (name "unconnected-(U1-ACGATE-Pad27)") (class "Default")
      (node (ref "U1") (pin "27") (pinfunction "ACGATE_27") (pintype "passive"))
    )
  )
)
